# untitled.net
KiCad netlist of a schematic drawn in EAGLE
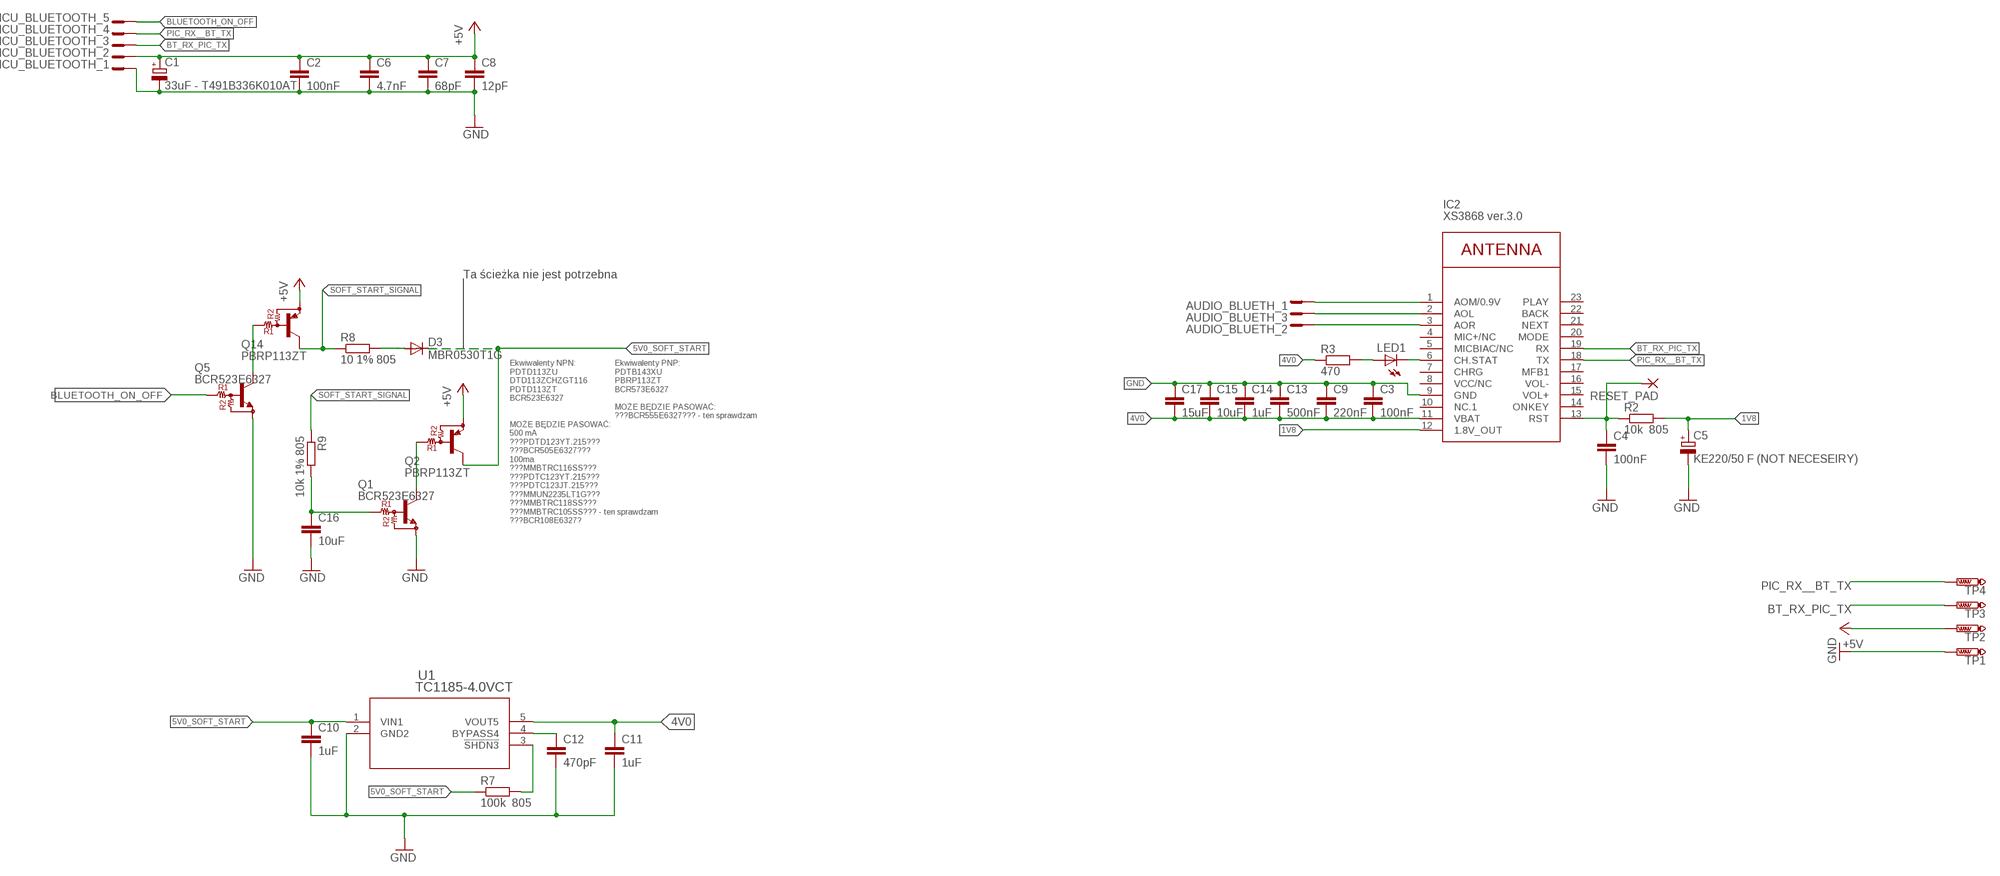
[diagram p0: schematic, sheet 1]

(export (version "E")
  (design (tool "Eeschema 10.0.6"))
  (components
    (comp (ref "AUDIO_BLUETH")
      (value "JST_3_PIN_B3B-PH-KS")
      (footprint "eagle-import:B3B-PH-KS")
      (libsource (lib "eagle-import") (part "JST_3_PIN_B3B-PH-KS"))
    )
    (comp (ref "C1")
      (value "33uF - T491B336K010AT")
      (footprint "eagle-import:SMC_C")
      (libsource (lib "eagle-import") (part "resistor_CPOL-EUSMCC"))
    )
    (comp (ref "C2")
      (value "100nF")
      (footprint "eagle-import:C0805")
      (libsource (lib "eagle-import") (part "resistor_C-EUC0805"))
    )
    (comp (ref "C3")
      (value "100nF")
      (footprint "eagle-import:C0805")
      (libsource (lib "eagle-import") (part "resistor_C-EUC0805"))
    )
    (comp (ref "C4")
      (value "100nF")
      (footprint "eagle-import:C0805")
      (libsource (lib "eagle-import") (part "resistor_C-EUC0805"))
    )
    (comp (ref "C5")
      (value "KE220/50 F (NOT NECESEIRY)")
      (footprint "eagle-import:PANASONIC_G")
      (libsource (lib "eagle-import") (part "CPOL-EUG"))
    )
    (comp (ref "C6")
      (value "4.7nF")
      (footprint "eagle-import:C0805")
      (libsource (lib "eagle-import") (part "resistor_C-EUC0805"))
    )
    (comp (ref "C7")
      (value "68pF")
      (footprint "eagle-import:C0805")
      (libsource (lib "eagle-import") (part "resistor_C-EUC0805"))
    )
    (comp (ref "C8")
      (value "12pF")
      (footprint "eagle-import:C0805")
      (libsource (lib "eagle-import") (part "resistor_C-EUC0805"))
    )
    (comp (ref "C9")
      (value "220nF")
      (footprint "eagle-import:C0805")
      (libsource (lib "eagle-import") (part "resistor_C-EUC0805"))
    )
    (comp (ref "C10")
      (value "1uF")
      (footprint "eagle-import:C0805")
      (libsource (lib "eagle-import") (part "resistor_C-EUC0805"))
    )
    (comp (ref "C11")
      (value "1uF")
      (footprint "eagle-import:C0805")
      (libsource (lib "eagle-import") (part "resistor_C-EUC0805"))
    )
    (comp (ref "C12")
      (value "470pF")
      (footprint "eagle-import:C0805")
      (libsource (lib "eagle-import") (part "resistor_C-EUC0805"))
    )
    (comp (ref "C13")
      (value "500nF")
      (footprint "eagle-import:C0805")
      (libsource (lib "eagle-import") (part "resistor_C-EUC0805"))
    )
    (comp (ref "C14")
      (value "1uF")
      (footprint "eagle-import:C0805")
      (libsource (lib "eagle-import") (part "resistor_C-EUC0805"))
    )
    (comp (ref "C15")
      (value "10uF")
      (footprint "eagle-import:C0805")
      (libsource (lib "eagle-import") (part "resistor_C-EUC0805"))
    )
    (comp (ref "C16")
      (value "10uF")
      (footprint "eagle-import:C0805")
      (libsource (lib "eagle-import") (part "C-EUC0805"))
    )
    (comp (ref "C17")
      (value "15uF")
      (footprint "eagle-import:C0805")
      (libsource (lib "eagle-import") (part "resistor_C-EUC0805"))
    )
    (comp (ref "D3")
      (value "MBR0530T1G")
      (footprint "eagle-import:SOD123")
      (libsource (lib "eagle-import") (part "MBR0520LT"))
    )
    (comp (ref "IC2")
      (value "XS3868 ver.3.0")
      (footprint "eagle-import:WIRELESS-BLUETOOTH-XS3868")
      (libsource (lib "eagle-import") (part "WIRELESS-BLUETOOTH-XS3868"))
    )
    (comp (ref "LED1")
      (value "LEDSML0805")
      (footprint "eagle-import:SML0805")
      (libsource (lib "eagle-import") (part "LEDSML0805"))
    )
    (comp (ref "MCU_BLUETOOTH")
      (value "JST_5_PIN_B5B-PH-KS")
      (footprint "eagle-import:B5B-PH-KS")
      (libsource (lib "eagle-import") (part "JST_5_PIN_B5B-PH-KS"))
    )
    (comp (ref "Q1")
      (value "BCR523E6327")
      (footprint "eagle-import:SOT-23")
      (libsource (lib "eagle-import") (part "PDTD113ZU"))
    )
    (comp (ref "Q2")
      (value "PBRP113ZT")
      (footprint "eagle-import:SOT-23")
      (libsource (lib "eagle-import") (part "PDTB143XU"))
    )
    (comp (ref "Q5")
      (value "BCR523E6327")
      (footprint "eagle-import:SOT-23")
      (libsource (lib "eagle-import") (part "PDTD113ZU"))
    )
    (comp (ref "Q14")
      (value "PBRP113ZT")
      (footprint "eagle-import:SOT-23")
      (libsource (lib "eagle-import") (part "PDTB143XU"))
    )
    (comp (ref "R2")
      (value "10k 805")
      (footprint "eagle-import:M0805")
      (libsource (lib "eagle-import") (part "R-EU_M0805"))
    )
    (comp (ref "R3")
      (value "470")
      (footprint "eagle-import:M0805")
      (libsource (lib "eagle-import") (part "R-EU_M0805"))
    )
    (comp (ref "R7")
      (value "100k 805")
      (footprint "eagle-import:M0805")
      (libsource (lib "eagle-import") (part "R-EU_M0805"))
    )
    (comp (ref "R8")
      (value "10 1% 805")
      (footprint "eagle-import:M0805")
      (libsource (lib "eagle-import") (part "R-EU_M0805"))
    )
    (comp (ref "R9")
      (value "10k 1% 805")
      (footprint "eagle-import:M0805")
      (libsource (lib "eagle-import") (part "R-EU_M0805"))
    )
    (comp (ref "RESET_PAD")
      (value "SMD2")
      (footprint "eagle-import:SMD1,27-2,54")
      (libsource (lib "eagle-import") (part "SMD2"))
    )
    (comp (ref "TP1")
      (value "PTR1B1,27")
      (footprint "eagle-import:B1,27")
      (libsource (lib "eagle-import") (part "PTR1B1,27"))
    )
    (comp (ref "TP2")
      (value "PTR1B1,27")
      (footprint "eagle-import:B1,27")
      (libsource (lib "eagle-import") (part "PTR1B1,27"))
    )
    (comp (ref "TP3")
      (value "PTR1B1,27")
      (footprint "eagle-import:B1,27")
      (libsource (lib "eagle-import") (part "PTR1B1,27"))
    )
    (comp (ref "TP4")
      (value "PTR1B1,27")
      (footprint "eagle-import:B1,27")
      (libsource (lib "eagle-import") (part "PTR1B1,27"))
    )
    (comp (ref "U1")
      (value "TC1185-4.0VCT")
      (footprint "eagle-import:SOT-23-5_MC-M")
      (fields (field (name "MANUFACTURER_PART_NUMBER") "TC1185X.XXCT713"))
      (libsource (lib "eagle-import") (part "TC1185-X.XXCT713SOT-23-5_MC-M"))
    )
  )
  (nets
    (net (code "1") (name "+5V") (class "Default")
      (node (ref "C1") (pin "+") (pinfunction "+_+") (pintype "passive"))
      (node (ref "C2") (pin "1") (pinfunction "1_1") (pintype "passive"))
      (node (ref "C6") (pin "1") (pinfunction "1_1") (pintype "passive"))
      (node (ref "C7") (pin "1") (pinfunction "1_1") (pintype "passive"))
      (node (ref "C8") (pin "1") (pinfunction "1_1") (pintype "passive"))
      (node (ref "MCU_BLUETOOTH") (pin "P$2") (pinfunction "P$1_P$2") (pintype "bidirectional"))
      (node (ref "Q14") (pin "2") (pinfunction "E_2") (pintype "passive"))
      (node (ref "Q2") (pin "2") (pinfunction "E_2") (pintype "passive"))
      (node (ref "TP2") (pin "TP") (pinfunction "TP_TP") (pintype "input"))
    )
    (net (code "2") (name "1V8") (class "Default")
      (node (ref "C5") (pin "+") (pinfunction "+_+") (pintype "passive"))
      (node (ref "IC2") (pin "12") (pinfunction "1.8V_OUT_12") (pintype "power_in"))
      (node (ref "R2") (pin "2") (pinfunction "2_2") (pintype "passive"))
    )
    (net (code "3") (name "4V0") (class "Default")
      (node (ref "C11") (pin "1") (pinfunction "1_1") (pintype "passive"))
      (node (ref "C13") (pin "2") (pinfunction "2_2") (pintype "passive"))
      (node (ref "C14") (pin "2") (pinfunction "2_2") (pintype "passive"))
      (node (ref "C15") (pin "2") (pinfunction "2_2") (pintype "passive"))
      (node (ref "C17") (pin "2") (pinfunction "2_2") (pintype "passive"))
      (node (ref "C3") (pin "2") (pinfunction "2_2") (pintype "passive"))
      (node (ref "C9") (pin "2") (pinfunction "2_2") (pintype "passive"))
      (node (ref "IC2") (pin "11") (pinfunction "VBAT_11") (pintype "power_in"))
      (node (ref "R3") (pin "1") (pinfunction "1_1") (pintype "passive"))
      (node (ref "U1") (pin "5") (pinfunction "VOUT5_5") (pintype "passive"))
    )
    (net (code "4") (name "5V0_SOFT_START") (class "Default")
      (node (ref "C10") (pin "1") (pinfunction "1_1") (pintype "passive"))
      (node (ref "D3") (pin "C") (pinfunction "C_C") (pintype "passive"))
      (node (ref "Q2") (pin "3") (pinfunction "C_3") (pintype "passive"))
      (node (ref "R7") (pin "1") (pinfunction "1_1") (pintype "passive"))
      (node (ref "U1") (pin "1") (pinfunction "VIN1_1") (pintype "passive"))
    )
    (net (code "5") (name "BLUETOOTH_ON_OFF") (class "Default")
      (node (ref "MCU_BLUETOOTH") (pin "P$5") (pinfunction "P$1_P$5") (pintype "bidirectional"))
      (node (ref "Q5") (pin "1") (pinfunction "B_1") (pintype "passive"))
    )
    (net (code "6") (name "BT_RX_PIC_TX") (class "Default")
      (node (ref "IC2") (pin "19") (pinfunction "RX_19") (pintype "bidirectional"))
      (node (ref "MCU_BLUETOOTH") (pin "P$3") (pinfunction "P$1_P$3") (pintype "bidirectional"))
      (node (ref "TP3") (pin "TP") (pinfunction "TP_TP") (pintype "input"))
    )
    (net (code "7") (name "GND") (class "Default")
      (node (ref "C1") (pin "-") (pinfunction "-_-") (pintype "passive"))
      (node (ref "C10") (pin "2") (pinfunction "2_2") (pintype "passive"))
      (node (ref "C11") (pin "2") (pinfunction "2_2") (pintype "passive"))
      (node (ref "C12") (pin "2") (pinfunction "2_2") (pintype "passive"))
      (node (ref "C13") (pin "1") (pinfunction "1_1") (pintype "passive"))
      (node (ref "C14") (pin "1") (pinfunction "1_1") (pintype "passive"))
      (node (ref "C15") (pin "1") (pinfunction "1_1") (pintype "passive"))
      (node (ref "C16") (pin "2") (pinfunction "2_2") (pintype "passive"))
      (node (ref "C17") (pin "1") (pinfunction "1_1") (pintype "passive"))
      (node (ref "C2") (pin "2") (pinfunction "2_2") (pintype "passive"))
      (node (ref "C3") (pin "1") (pinfunction "1_1") (pintype "passive"))
      (node (ref "C4") (pin "2") (pinfunction "2_2") (pintype "passive"))
      (node (ref "C5") (pin "-") (pinfunction "-_-") (pintype "passive"))
      (node (ref "C6") (pin "2") (pinfunction "2_2") (pintype "passive"))
      (node (ref "C7") (pin "2") (pinfunction "2_2") (pintype "passive"))
      (node (ref "C8") (pin "2") (pinfunction "2_2") (pintype "passive"))
      (node (ref "C9") (pin "1") (pinfunction "1_1") (pintype "passive"))
      (node (ref "IC2") (pin "9") (pinfunction "GND_9") (pintype "power_in"))
      (node (ref "MCU_BLUETOOTH") (pin "P$1") (pinfunction "P$1_P$1") (pintype "bidirectional"))
      (node (ref "Q1") (pin "2") (pinfunction "E_2") (pintype "passive"))
      (node (ref "Q5") (pin "2") (pinfunction "E_2") (pintype "passive"))
      (node (ref "TP1") (pin "TP") (pinfunction "TP_TP") (pintype "input"))
      (node (ref "U1") (pin "2") (pinfunction "GND2_2") (pintype "passive"))
    )
    (net (code "8") (name "Net-(AUDIO_BLUETHB-P$1)") (class "Default")
      (node (ref "AUDIO_BLUETH") (pin "P$2") (pinfunction "P$1_P$2") (pintype "bidirectional"))
      (node (ref "IC2") (pin "3") (pinfunction "AOR_3") (pintype "output"))
    )
    (net (code "9") (name "Net-(AUDIO_BLUETHC-P$1)") (class "Default")
      (node (ref "AUDIO_BLUETH") (pin "P$3") (pinfunction "P$1_P$3") (pintype "bidirectional"))
      (node (ref "IC2") (pin "2") (pinfunction "AOL_2") (pintype "output"))
    )
    (net (code "10") (name "Net-(D3-PadA)") (class "Default")
      (node (ref "D3") (pin "A") (pinfunction "A_A") (pintype "passive"))
      (node (ref "R8") (pin "2") (pinfunction "2_2") (pintype "passive"))
    )
    (net (code "11") (name "Net-(IC2-AOM{slash}0.9V)") (class "Default")
      (node (ref "AUDIO_BLUETH") (pin "P$1") (pinfunction "P$1_P$1") (pintype "bidirectional"))
      (node (ref "IC2") (pin "1") (pinfunction "AOM/0.9V_1") (pintype "power_in"))
    )
    (net (code "12") (name "Net-(IC2-CH.STAT)") (class "Default")
      (node (ref "IC2") (pin "6") (pinfunction "CH.STAT_6") (pintype "bidirectional"))
      (node (ref "LED1") (pin "C") (pinfunction "C_C") (pintype "passive"))
    )
    (net (code "13") (name "Net-(IC2-RST)") (class "Default")
      (node (ref "C4") (pin "1") (pinfunction "1_1") (pintype "passive"))
      (node (ref "IC2") (pin "13") (pinfunction "RST_13") (pintype "power_in"))
      (node (ref "R2") (pin "1") (pinfunction "1_1") (pintype "passive"))
      (node (ref "RESET_PAD") (pin "1") (pinfunction "P_1") (pintype "passive"))
    )
    (net (code "14") (name "Net-(LED1-PadA)") (class "Default")
      (node (ref "LED1") (pin "A") (pinfunction "A_A") (pintype "passive"))
      (node (ref "R3") (pin "2") (pinfunction "2_2") (pintype "passive"))
    )
    (net (code "15") (name "Net-(Q1-B)") (class "Default")
      (node (ref "C16") (pin "1") (pinfunction "1_1") (pintype "passive"))
      (node (ref "Q1") (pin "1") (pinfunction "B_1") (pintype "passive"))
      (node (ref "R9") (pin "2") (pinfunction "2_2") (pintype "passive"))
    )
    (net (code "16") (name "Net-(Q1-C)") (class "Default")
      (node (ref "Q1") (pin "3") (pinfunction "C_3") (pintype "passive"))
      (node (ref "Q2") (pin "1") (pinfunction "B_1") (pintype "passive"))
    )
    (net (code "17") (name "Net-(Q14-B)") (class "Default")
      (node (ref "Q14") (pin "1") (pinfunction "B_1") (pintype "passive"))
      (node (ref "Q5") (pin "3") (pinfunction "C_3") (pintype "passive"))
    )
    (net (code "18") (name "Net-(U1-BYPASS4)") (class "Default")
      (node (ref "C12") (pin "1") (pinfunction "1_1") (pintype "passive"))
      (node (ref "U1") (pin "4") (pinfunction "BYPASS4_4") (pintype "passive"))
    )
    (net (code "19") (name "Net-(U1-~{SHDN3})") (class "Default")
      (node (ref "R7") (pin "2") (pinfunction "2_2") (pintype "passive"))
      (node (ref "U1") (pin "3") (pinfunction "~{SHDN3}_3") (pintype "passive"))
    )
    (net (code "20") (name "PIC_RX__BT_TX") (class "Default")
      (node (ref "IC2") (pin "18") (pinfunction "TX_18") (pintype "bidirectional"))
      (node (ref "MCU_BLUETOOTH") (pin "P$4") (pinfunction "P$1_P$4") (pintype "bidirectional"))
      (node (ref "TP4") (pin "TP") (pinfunction "TP_TP") (pintype "input"))
    )
    (net (code "21") (name "SOFT_START_SIGNAL") (class "Default")
      (node (ref "Q14") (pin "3") (pinfunction "C_3") (pintype "passive"))
      (node (ref "R8") (pin "1") (pinfunction "1_1") (pintype "passive"))
      (node (ref "R9") (pin "1") (pinfunction "1_1") (pintype "passive"))
    )
    (net (code "22") (name "unconnected-(IC2-BACK-Pad22)") (class "Default")
      (node (ref "IC2") (pin "22") (pinfunction "BACK_22") (pintype "bidirectional"))
    )
    (net (code "23") (name "unconnected-(IC2-CHRG-Pad7)") (class "Default")
      (node (ref "IC2") (pin "7") (pinfunction "CHRG_7") (pintype "bidirectional"))
    )
    (net (code "24") (name "unconnected-(IC2-MFB1-Pad17)") (class "Default")
      (node (ref "IC2") (pin "17") (pinfunction "MFB1_17") (pintype "passive"))
    )
    (net (code "25") (name "unconnected-(IC2-MIC+{slash}NC-Pad4)") (class "Default")
      (node (ref "IC2") (pin "4") (pinfunction "MIC+/NC_4") (pintype "bidirectional"))
    )
    (net (code "26") (name "unconnected-(IC2-MICBIAC{slash}NC-Pad5)") (class "Default")
      (node (ref "IC2") (pin "5") (pinfunction "MICBIAC/NC_5") (pintype "bidirectional"))
    )
    (net (code "27") (name "unconnected-(IC2-MODE-Pad20)") (class "Default")
      (node (ref "IC2") (pin "20") (pinfunction "MODE_20") (pintype "passive"))
    )
    (net (code "28") (name "unconnected-(IC2-NC.1-Pad10)") (class "Default")
      (node (ref "IC2") (pin "10") (pinfunction "NC.1_10") (pintype "passive"))
    )
    (net (code "29") (name "unconnected-(IC2-NEXT-Pad21)") (class "Default")
      (node (ref "IC2") (pin "21") (pinfunction "NEXT_21") (pintype "bidirectional"))
    )
    (net (code "30") (name "unconnected-(IC2-ONKEY-Pad14)") (class "Default")
      (node (ref "IC2") (pin "14") (pinfunction "ONKEY_14") (pintype "passive"))
    )
    (net (code "31") (name "unconnected-(IC2-PLAY-Pad23)") (class "Default")
      (node (ref "IC2") (pin "23") (pinfunction "PLAY_23") (pintype "bidirectional"))
    )
    (net (code "32") (name "unconnected-(IC2-VCC{slash}NC-Pad8)") (class "Default")
      (node (ref "IC2") (pin "8") (pinfunction "VCC/NC_8") (pintype "bidirectional"))
    )
    (net (code "33") (name "unconnected-(IC2-VOL+-Pad15)") (class "Default")
      (node (ref "IC2") (pin "15") (pinfunction "VOL+_15") (pintype "bidirectional"))
    )
    (net (code "34") (name "unconnected-(IC2-VOL--Pad16)") (class "Default")
      (node (ref "IC2") (pin "16") (pinfunction "VOL-_16") (pintype "bidirectional"))
    )
  )
)
